# FPGA_Connector.net
KiCad netlist of a schematic drawn in Altium Designer
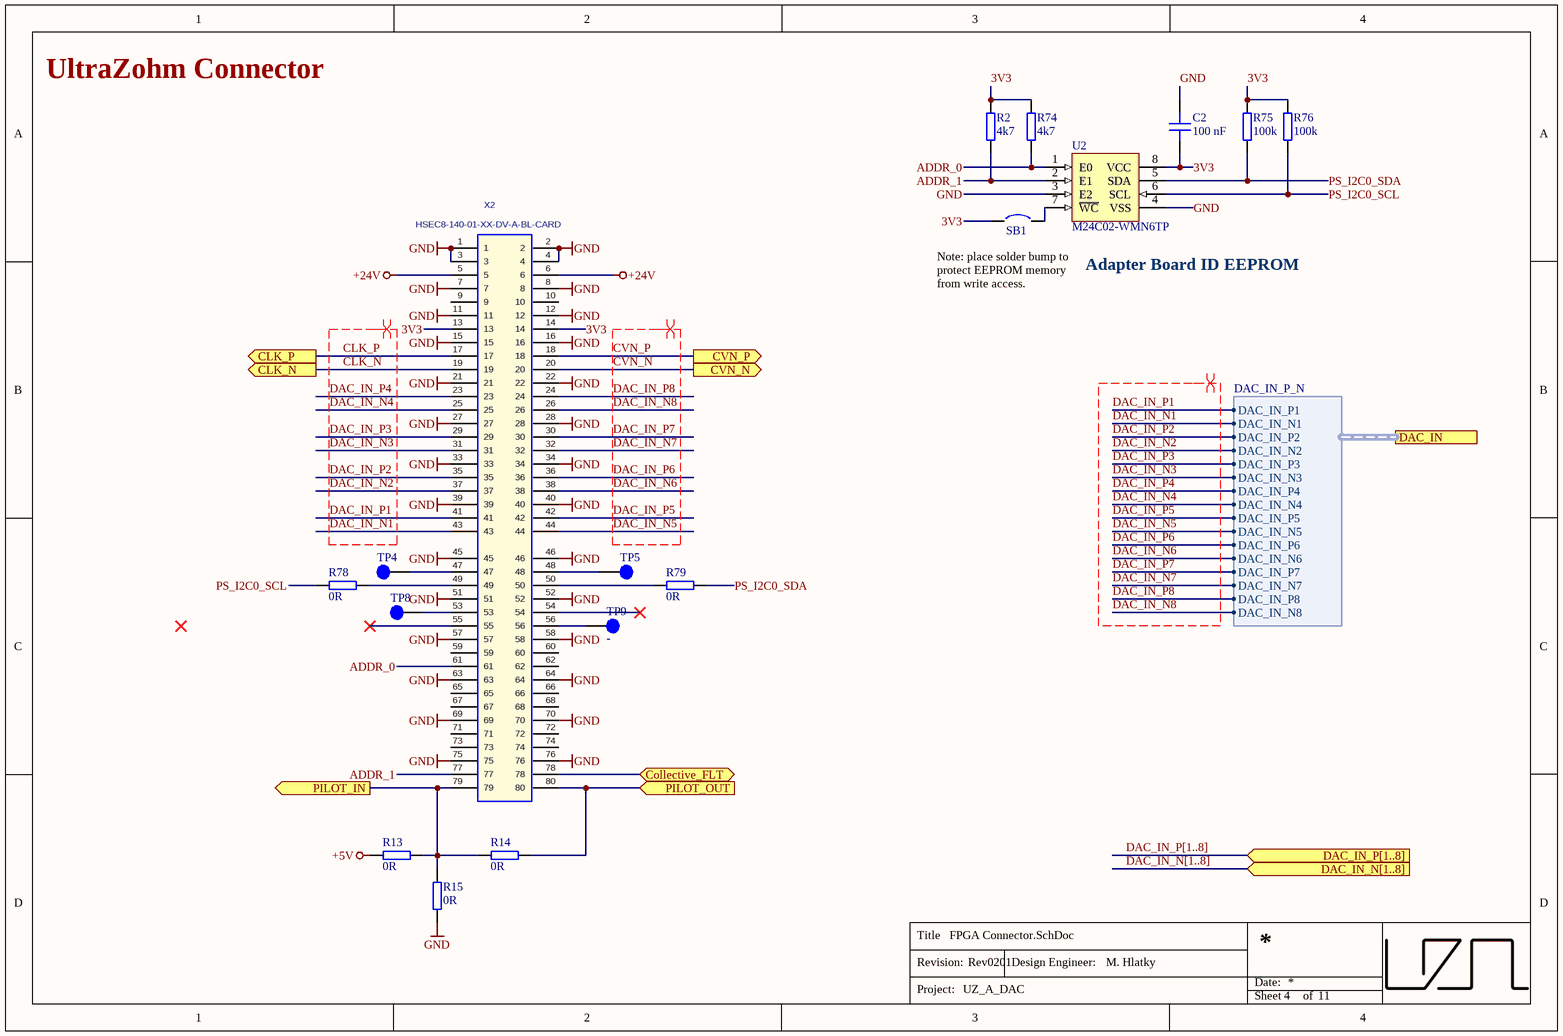
[diagram p0: FPGA Connector.SchDoc]

(export (version "E")
  (design (tool "Eeschema 10.0.6"))
  (components
    (comp (ref "C2")
      (value "100 nF")
      (footprint "C_0603")
      (description "Capacitor 0603, 6.3 VDC, 100 nF, X5R")
      (fields
        (field (name "MANUFACTURER PART NUMBER") "C0603C104K9PACTU")
        (field (name "MANUFACTURER") "KEMET")
        (field (name "CREATED FROM") "MGremer")
      )
      (libsource (lib "user") (part "Capacitor"))
    )
    (comp (ref "R2")
      (value "4k7")
      (footprint "RES 0603_1608")
      (description "SMD resistor E24 series")
      (fields
        (field (name "MANUFACTURER PART NUMBER") "0603WAF4701T5E")
        (field (name "MANUFACTURER") "UNI-ROYAL")
        (field (name "CREATED FROM") "AGeiger")
      )
      (libsource (lib "user") (part "Resistor"))
    )
    (comp (ref "R13")
      (value "0R")
      (footprint "RES 0603_1608")
      (description "SMD resistor E24 series")
      (fields
        (field (name "MANUFACTURER PART NUMBER") "RC0603JR-070RL")
        (field (name "MANUFACTURER") "YAGEO")
        (field (name "CREATED FROM") "MGremer")
      )
      (libsource (lib "user") (part "Resistor"))
    )
    (comp (ref "R14")
      (value "0R")
      (footprint "RES 0603_1608")
      (description "SMD resistor E24 series")
      (fields
        (field (name "MANUFACTURER PART NUMBER") "RC0603JR-070RL")
        (field (name "MANUFACTURER") "YAGEO")
        (field (name "CREATED FROM") "MGremer")
      )
      (libsource (lib "user") (part "Resistor"))
    )
    (comp (ref "R15")
      (value "0R")
      (footprint "RES 0603_1608")
      (description "SMD resistor E24 series")
      (fields
        (field (name "MANUFACTURER PART NUMBER") "RC0603JR-070RL")
        (field (name "MANUFACTURER") "YAGEO")
        (field (name "CREATED FROM") "MGremer")
      )
      (libsource (lib "user") (part "Resistor"))
    )
    (comp (ref "R74")
      (value "4k7")
      (footprint "RES 0603_1608")
      (description "SMD resistor E24 series")
      (fields
        (field (name "MANUFACTURER PART NUMBER") "0603WAF4701T5E")
        (field (name "MANUFACTURER") "UNI-ROYAL")
        (field (name "CREATED FROM") "AGeiger")
      )
      (libsource (lib "user") (part "Resistor"))
    )
    (comp (ref "R75")
      (value "100k")
      (footprint "RES 0603_1608")
      (description "SMD resistor E24 series")
      (fields
        (field (name "MANUFACTURER PART NUMBER") "RK73B1JTTD104J")
        (field (name "MANUFACTURER") "KOA Speer")
        (field (name "CREATED FROM") "MGremer")
      )
      (libsource (lib "user") (part "Resistor"))
    )
    (comp (ref "R76")
      (value "100k")
      (footprint "RES 0603_1608")
      (description "SMD resistor E24 series")
      (fields
        (field (name "MANUFACTURER PART NUMBER") "RK73B1JTTD104J")
        (field (name "MANUFACTURER") "KOA Speer")
        (field (name "CREATED FROM") "MGremer")
      )
      (libsource (lib "user") (part "Resistor"))
    )
    (comp (ref "R78")
      (value "0R")
      (footprint "RES 0603_1608")
      (description "SMD resistor E24 series")
      (fields
        (field (name "MANUFACTURER PART NUMBER") "RC0603JR-070RL")
        (field (name "MANUFACTURER") "YAGEO")
        (field (name "CREATED FROM") "MGremer")
      )
      (libsource (lib "user") (part "Resistor"))
    )
    (comp (ref "R79")
      (value "0R")
      (footprint "RES 0603_1608")
      (description "SMD resistor E24 series")
      (fields
        (field (name "MANUFACTURER PART NUMBER") "RC0603JR-070RL")
        (field (name "MANUFACTURER") "YAGEO")
        (field (name "CREATED FROM") "MGremer")
      )
      (libsource (lib "user") (part "Resistor"))
    )
    (comp (ref "SB1")
      (value "Solder Bump 0603")
      (footprint "SB_0603")
      (fields (field (name "CREATED FROM") "AGeiger"))
      (libsource (lib "user") (part "Solder_Bump"))
    )
    (comp (ref "TP4")
      (value "-")
      (footprint "TP_1mm")
      (description "Test Point 1 mm")
      (fields (field (name "CREATED") "2018_06_25_AGeiger") (field (name "CREATED FROM") "MGremer"))
      (libsource (lib "user") (part "TP_1mm"))
    )
    (comp (ref "TP5")
      (value "-")
      (footprint "TP_1mm")
      (description "Test Point 1 mm")
      (fields (field (name "CREATED") "2018_06_25_AGeiger") (field (name "CREATED FROM") "MGremer"))
      (libsource (lib "user") (part "TP_1mm"))
    )
    (comp (ref "TP8")
      (value "-")
      (footprint "TP_1mm")
      (description "Test Point 1 mm")
      (fields (field (name "CREATED") "2018_06_25_AGeiger") (field (name "CREATED FROM") "MGremer"))
      (libsource (lib "user") (part "TP_1mm"))
    )
    (comp (ref "TP9")
      (value "-")
      (footprint "TP_1mm")
      (description "Test Point 1 mm")
      (fields (field (name "CREATED") "2018_06_25_AGeiger") (field (name "CREATED FROM") "MGremer"))
      (libsource (lib "user") (part "TP_1mm"))
    )
    (comp (ref "U2")
      (value "M24C02-WMN6TP")
      (footprint "D0008A_N")
      (description "2Kbit I2C SOP-8 EEPROM ROHS")
      (fields
        (field (name "MANUFACTURER") "STMicroelectronics")
        (field (name "LCSC PART NUMBER") "C7562")
        (field (name "CREATED FROM") "AGeiger")
      )
      (libsource (lib "user") (part "M24256"))
    )
    (comp (ref "X2")
      (value "HSEC8-140-01-XX-DV-A-BL-CARD")
      (footprint "HSEC8-140-01-XX-DV-A-BL-CARD")
      (description "Mating Card Layout for HSEC8-140-01-XX-DV-A-BL-CARD")
      (fields
        (field (name "MANUFACTURER") "SAMTEC")
        (field (name "CREATED") "2018_04_23_AGeiger")
        (field (name "CREATED FROM") "MHlatky")
      )
      (libsource (lib "user") (part "HSEC8-140-01-XX-DV-A-BL-CARD"))
    )
  )
  (nets
    (net (code "2") (name "+5V") (class "Default")
      (node (ref "R13") (pin "1") (pinfunction "1_1") (pintype "passive"))
    )
    (net (code "3") (name "+24V") (class "Default")
      (node (ref "X2") (pin "5") (pinfunction "5_5") (pintype "passive"))
      (node (ref "X2") (pin "6") (pinfunction "6_6") (pintype "passive"))
    )
    (net (code "4") (name "/3V3") (class "Default")
      (node (ref "C2") (pin "1") (pinfunction "1_1") (pintype "passive"))
      (node (ref "R2") (pin "2") (pinfunction "2_2") (pintype "passive"))
      (node (ref "R74") (pin "2") (pinfunction "2_2") (pintype "passive"))
      (node (ref "R75") (pin "2") (pinfunction "2_2") (pintype "passive"))
      (node (ref "R76") (pin "2") (pinfunction "2_2") (pintype "passive"))
      (node (ref "SB1") (pin "1") (pinfunction "1_1") (pintype "passive"))
      (node (ref "U2") (pin "8") (pinfunction "VCC_8") (pintype "power_in"))
      (node (ref "X2") (pin "13") (pinfunction "13_13") (pintype "passive"))
      (node (ref "X2") (pin "14") (pinfunction "14_14") (pintype "passive"))
    )
    (net (code "5") (name "/ADDR_0") (class "Default")
      (node (ref "R74") (pin "1") (pinfunction "1_1") (pintype "passive"))
      (node (ref "U2") (pin "1") (pinfunction "E0_1") (pintype "input"))
      (node (ref "X2") (pin "61") (pinfunction "61_61") (pintype "passive"))
    )
    (net (code "6") (name "/ADDR_1") (class "Default")
      (node (ref "R2") (pin "1") (pinfunction "1_1") (pintype "passive"))
      (node (ref "U2") (pin "2") (pinfunction "E1_2") (pintype "input"))
      (node (ref "X2") (pin "77") (pinfunction "77_77") (pintype "passive"))
    )
    (net (code "7") (name "/CLK_N") (class "Default")
      (node (ref "X2") (pin "19") (pinfunction "19_19") (pintype "passive"))
    )
    (net (code "8") (name "/CLK_P") (class "Default")
      (node (ref "X2") (pin "17") (pinfunction "17_17") (pintype "passive"))
    )
    (net (code "9") (name "/CVN_N") (class "Default")
      (node (ref "X2") (pin "20") (pinfunction "20_20") (pintype "passive"))
    )
    (net (code "10") (name "/CVN_P") (class "Default")
      (node (ref "X2") (pin "18") (pinfunction "18_18") (pintype "passive"))
    )
    (net (code "11") (name "/Collective_FLT") (class "Default")
      (node (ref "X2") (pin "78") (pinfunction "78_78") (pintype "passive"))
    )
    (net (code "12") (name "/DAC_IN_N1") (class "Default")
      (node (ref "X2") (pin "43") (pinfunction "43_43") (pintype "passive"))
    )
    (net (code "13") (name "/DAC_IN_N2") (class "Default")
      (node (ref "X2") (pin "37") (pinfunction "37_37") (pintype "passive"))
    )
    (net (code "14") (name "/DAC_IN_N3") (class "Default")
      (node (ref "X2") (pin "31") (pinfunction "31_31") (pintype "passive"))
    )
    (net (code "15") (name "/DAC_IN_N4") (class "Default")
      (node (ref "X2") (pin "25") (pinfunction "25_25") (pintype "passive"))
    )
    (net (code "16") (name "/DAC_IN_N5") (class "Default")
      (node (ref "X2") (pin "44") (pinfunction "44_44") (pintype "passive"))
    )
    (net (code "17") (name "/DAC_IN_N6") (class "Default")
      (node (ref "X2") (pin "38") (pinfunction "38_38") (pintype "passive"))
    )
    (net (code "18") (name "/DAC_IN_N7") (class "Default")
      (node (ref "X2") (pin "32") (pinfunction "32_32") (pintype "passive"))
    )
    (net (code "19") (name "/DAC_IN_N8") (class "Default")
      (node (ref "X2") (pin "26") (pinfunction "26_26") (pintype "passive"))
    )
    (net (code "21") (name "/DAC_IN_P1") (class "Default")
      (node (ref "X2") (pin "41") (pinfunction "41_41") (pintype "passive"))
    )
    (net (code "22") (name "/DAC_IN_P2") (class "Default")
      (node (ref "X2") (pin "35") (pinfunction "35_35") (pintype "passive"))
    )
    (net (code "23") (name "/DAC_IN_P3") (class "Default")
      (node (ref "X2") (pin "29") (pinfunction "29_29") (pintype "passive"))
    )
    (net (code "24") (name "/DAC_IN_P4") (class "Default")
      (node (ref "X2") (pin "23") (pinfunction "23_23") (pintype "passive"))
    )
    (net (code "25") (name "/DAC_IN_P5") (class "Default")
      (node (ref "X2") (pin "42") (pinfunction "42_42") (pintype "passive"))
    )
    (net (code "26") (name "/DAC_IN_P6") (class "Default")
      (node (ref "X2") (pin "36") (pinfunction "36_36") (pintype "passive"))
    )
    (net (code "27") (name "/DAC_IN_P7") (class "Default")
      (node (ref "X2") (pin "30") (pinfunction "30_30") (pintype "passive"))
    )
    (net (code "28") (name "/DAC_IN_P8") (class "Default")
      (node (ref "X2") (pin "24") (pinfunction "24_24") (pintype "passive"))
    )
    (net (code "30") (name "/PILOT_IN") (class "Default")
      (node (ref "R13") (pin "2") (pinfunction "2_2") (pintype "passive"))
      (node (ref "R14") (pin "1") (pinfunction "1_1") (pintype "passive"))
      (node (ref "R15") (pin "2") (pinfunction "2_2") (pintype "passive"))
      (node (ref "X2") (pin "79") (pinfunction "79_79") (pintype "passive"))
    )
    (net (code "31") (name "/PILOT_OUT") (class "Default")
      (node (ref "R14") (pin "2") (pinfunction "2_2") (pintype "passive"))
      (node (ref "X2") (pin "80") (pinfunction "80_80") (pintype "passive"))
    )
    (net (code "32") (name "/PS_I2C0_SCL") (class "Default")
      (node (ref "R76") (pin "1") (pinfunction "1_1") (pintype "passive"))
      (node (ref "R78") (pin "1") (pinfunction "1_1") (pintype "passive"))
      (node (ref "U2") (pin "6") (pinfunction "SCL_6") (pintype "input"))
    )
    (net (code "33") (name "/PS_I2C0_SDA") (class "Default")
      (node (ref "R75") (pin "1") (pinfunction "1_1") (pintype "passive"))
      (node (ref "R79") (pin "2") (pinfunction "2_2") (pintype "passive"))
      (node (ref "U2") (pin "5") (pinfunction "SDA_5") (pintype "open_collector"))
    )
    (net (code "35") (name "GND") (class "Default")
      (node (ref "C2") (pin "2") (pinfunction "2_2") (pintype "passive"))
      (node (ref "R15") (pin "1") (pinfunction "1_1") (pintype "passive"))
      (node (ref "U2") (pin "3") (pinfunction "E2_3") (pintype "input"))
      (node (ref "U2") (pin "4") (pinfunction "VSS_4") (pintype "power_in"))
      (node (ref "X2") (pin "1") (pinfunction "1_1") (pintype "passive"))
      (node (ref "X2") (pin "11") (pinfunction "11_11") (pintype "passive"))
      (node (ref "X2") (pin "12") (pinfunction "12_12") (pintype "passive"))
      (node (ref "X2") (pin "15") (pinfunction "15_15") (pintype "passive"))
      (node (ref "X2") (pin "16") (pinfunction "16_16") (pintype "passive"))
      (node (ref "X2") (pin "2") (pinfunction "2_2") (pintype "passive"))
      (node (ref "X2") (pin "21") (pinfunction "21_21") (pintype "passive"))
      (node (ref "X2") (pin "22") (pinfunction "22_22") (pintype "passive"))
      (node (ref "X2") (pin "27") (pinfunction "27_27") (pintype "passive"))
      (node (ref "X2") (pin "28") (pinfunction "28_28") (pintype "passive"))
      (node (ref "X2") (pin "3") (pinfunction "3_3") (pintype "passive"))
      (node (ref "X2") (pin "33") (pinfunction "33_33") (pintype "passive"))
      (node (ref "X2") (pin "34") (pinfunction "34_34") (pintype "passive"))
      (node (ref "X2") (pin "39") (pinfunction "39_39") (pintype "passive"))
      (node (ref "X2") (pin "4") (pinfunction "4_4") (pintype "passive"))
      (node (ref "X2") (pin "40") (pinfunction "40_40") (pintype "passive"))
      (node (ref "X2") (pin "45") (pinfunction "45_45") (pintype "passive"))
      (node (ref "X2") (pin "46") (pinfunction "46_46") (pintype "passive"))
      (node (ref "X2") (pin "51") (pinfunction "51_51") (pintype "passive"))
      (node (ref "X2") (pin "52") (pinfunction "52_52") (pintype "passive"))
      (node (ref "X2") (pin "57") (pinfunction "57_57") (pintype "passive"))
      (node (ref "X2") (pin "58") (pinfunction "58_58") (pintype "passive"))
      (node (ref "X2") (pin "63") (pinfunction "63_63") (pintype "passive"))
      (node (ref "X2") (pin "64") (pinfunction "64_64") (pintype "passive"))
      (node (ref "X2") (pin "69") (pinfunction "69_69") (pintype "passive"))
      (node (ref "X2") (pin "7") (pinfunction "7_7") (pintype "passive"))
      (node (ref "X2") (pin "70") (pinfunction "70_70") (pintype "passive"))
      (node (ref "X2") (pin "75") (pinfunction "75_75") (pintype "passive"))
      (node (ref "X2") (pin "76") (pinfunction "76_76") (pintype "passive"))
      (node (ref "X2") (pin "8") (pinfunction "8_8") (pintype "passive"))
    )
    (net (code "36") (name "Net-(R78-Pad2)") (class "Default")
      (node (ref "R78") (pin "2") (pinfunction "2_2") (pintype "passive"))
      (node (ref "X2") (pin "49") (pinfunction "49_49") (pintype "passive"))
    )
    (net (code "37") (name "Net-(R79-Pad1)") (class "Default")
      (node (ref "R79") (pin "1") (pinfunction "1_1") (pintype "passive"))
      (node (ref "X2") (pin "50") (pinfunction "50_50") (pintype "passive"))
    )
    (net (code "38") (name "Net-(TP4-Pad1)") (class "Default")
      (node (ref "TP4") (pin "1") (pintype "passive"))
      (node (ref "X2") (pin "47") (pinfunction "47_47") (pintype "passive"))
    )
    (net (code "39") (name "Net-(TP5-Pad1)") (class "Default")
      (node (ref "TP5") (pin "1") (pintype "passive"))
      (node (ref "X2") (pin "48") (pinfunction "48_48") (pintype "passive"))
    )
    (net (code "40") (name "Net-(TP8-Pad1)") (class "Default")
      (node (ref "TP8") (pin "1") (pintype "passive"))
      (node (ref "X2") (pin "53") (pinfunction "53_53") (pintype "passive"))
    )
    (net (code "41") (name "Net-(TP9-Pad1)") (class "Default")
      (node (ref "TP9") (pin "1") (pintype "passive"))
      (node (ref "X2") (pin "56") (pinfunction "56_56") (pintype "passive"))
    )
    (net (code "42") (name "Net-(U2-~{WC})") (class "Default")
      (node (ref "SB1") (pin "2") (pinfunction "2_2") (pintype "passive"))
      (node (ref "U2") (pin "7") (pinfunction "~{WC}_7") (pintype "input"))
    )
    (net (code "43") (name "unconnected-(X2-Pad9)") (class "Default")
      (node (ref "X2") (pin "9") (pinfunction "9_9") (pintype "passive"))
    )
    (net (code "44") (name "unconnected-(X2-Pad10)") (class "Default")
      (node (ref "X2") (pin "10") (pinfunction "10_10") (pintype "passive"))
    )
    (net (code "45") (name "unconnected-(X2-Pad54)") (class "Default")
      (node (ref "X2") (pin "54") (pinfunction "54_54") (pintype "passive+no_connect"))
    )
    (net (code "46") (name "unconnected-(X2-Pad55)") (class "Default")
      (node (ref "X2") (pin "55") (pinfunction "55_55") (pintype "passive+no_connect"))
    )
    (net (code "47") (name "unconnected-(X2-Pad59)") (class "Default")
      (node (ref "X2") (pin "59") (pinfunction "59_59") (pintype "passive"))
    )
    (net (code "48") (name "unconnected-(X2-Pad60)") (class "Default")
      (node (ref "X2") (pin "60") (pinfunction "60_60") (pintype "passive"))
    )
    (net (code "49") (name "unconnected-(X2-Pad62)") (class "Default")
      (node (ref "X2") (pin "62") (pinfunction "62_62") (pintype "passive"))
    )
    (net (code "50") (name "unconnected-(X2-Pad65)") (class "Default")
      (node (ref "X2") (pin "65") (pinfunction "65_65") (pintype "passive"))
    )
    (net (code "51") (name "unconnected-(X2-Pad66)") (class "Default")
      (node (ref "X2") (pin "66") (pinfunction "66_66") (pintype "passive"))
    )
    (net (code "52") (name "unconnected-(X2-Pad67)") (class "Default")
      (node (ref "X2") (pin "67") (pinfunction "67_67") (pintype "passive"))
    )
    (net (code "53") (name "unconnected-(X2-Pad68)") (class "Default")
      (node (ref "X2") (pin "68") (pinfunction "68_68") (pintype "passive"))
    )
    (net (code "54") (name "unconnected-(X2-Pad71)") (class "Default")
      (node (ref "X2") (pin "71") (pinfunction "71_71") (pintype "passive"))
    )
    (net (code "55") (name "unconnected-(X2-Pad72)") (class "Default")
      (node (ref "X2") (pin "72") (pinfunction "72_72") (pintype "passive"))
    )
    (net (code "56") (name "unconnected-(X2-Pad73)") (class "Default")
      (node (ref "X2") (pin "73") (pinfunction "73_73") (pintype "passive"))
    )
    (net (code "57") (name "unconnected-(X2-Pad74)") (class "Default")
      (node (ref "X2") (pin "74") (pinfunction "74_74") (pintype "passive"))
    )
  )
)
